# lm2700.net
KiCad netlist of a schematic drawn in Altium Designer
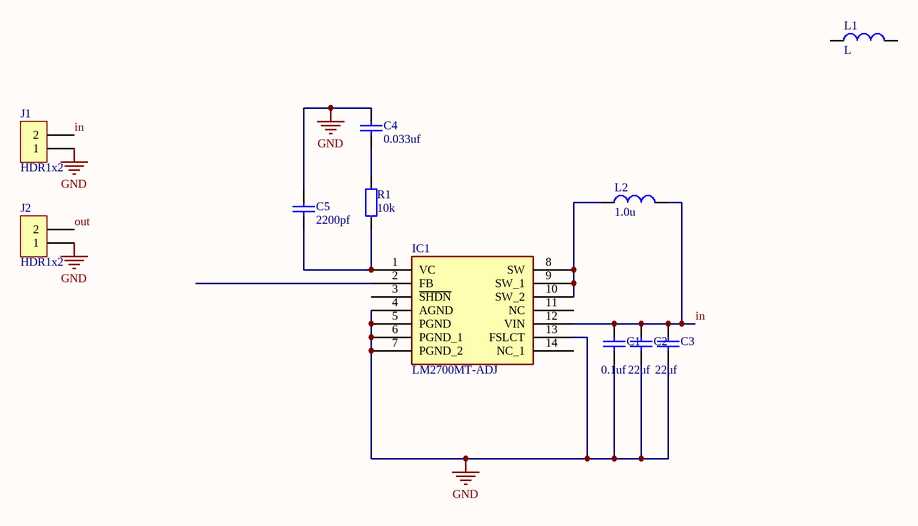
[diagram p0: lm2700.SchDoc]

(export (version "E")
  (design (tool "Eeschema 10.0.6"))
  (components
    (comp (ref "C1")
      (value "0.1uf")
      (footprint "basic:2220")
      (description "电容")
      (libsource (lib "basic") (part "C"))
    )
    (comp (ref "C2")
      (value "22uf")
      (footprint "basic:2220")
      (description "电容")
      (libsource (lib "basic") (part "C"))
    )
    (comp (ref "C3")
      (value "22uf")
      (footprint "basic:2220")
      (description "电容")
      (libsource (lib "basic") (part "C"))
    )
    (comp (ref "C4")
      (value "0.033uf")
      (footprint "basic:2220")
      (description "电容")
      (libsource (lib "basic") (part "C"))
    )
    (comp (ref "C5")
      (value "2200pf")
      (footprint "basic:2220")
      (description "电容")
      (libsource (lib "basic") (part "C"))
    )
    (comp (ref "IC1")
      (value "LM2700MT-ADJ")
      (footprint "SamacSys:SOP65P640X120-14N")
      (description "Integrated Circuit")
      (fields
        (field (name "MOUSER PART NUMBER") "926-LM2700MT-ADJ")
        (field (name "RS PART NUMBER") "4432079")
      )
      (libsource (lib "SamacSys") (part "LM2700MT-ADJ"))
    )
    (comp (ref "J1")
      (value "HDR1x2")
      (footprint "PIN-2-2.54-1.0")
      (description "Connector")
      (libsource (lib "General") (part "HDR1x2"))
    )
    (comp (ref "J2")
      (value "HDR1x2")
      (footprint "PIN-2-2.54-1.0")
      (description "Connector")
      (libsource (lib "General") (part "HDR1x2"))
    )
    (comp (ref "L1")
      (value "L")
      (footprint "L4R7")
      (description "大号贴片电感")
      (libsource (lib "basic") (part "L"))
    )
    (comp (ref "L2")
      (value "1.0u")
      (footprint "L4R7")
      (description "大号贴片电感")
      (libsource (lib "basic") (part "L"))
    )
    (comp (ref "R1")
      (value "10k")
      (footprint "basic:2220")
      (description "电阻")
      (libsource (lib "basic") (part "R"))
    )
  )
  (nets
    (net (code "1") (name "/in") (class "Default")
      (node (ref "C1") (pin "2") (pinfunction "2_2") (pintype "passive"))
      (node (ref "C2") (pin "2") (pinfunction "2_2") (pintype "passive"))
      (node (ref "C3") (pin "2") (pinfunction "2_2") (pintype "passive"))
      (node (ref "IC1") (pin "12") (pinfunction "VIN_12") (pintype "passive"))
      (node (ref "J1") (pin "2") (pinfunction "2_2") (pintype "passive"))
      (node (ref "L2") (pin "2") (pinfunction "2_2") (pintype "passive"))
    )
    (net (code "2") (name "/out") (class "Default")
      (node (ref "J2") (pin "2") (pinfunction "2_2") (pintype "passive"))
    )
    (net (code "3") (name "GND") (class "Default")
      (node (ref "C1") (pin "1") (pinfunction "1_1") (pintype "passive"))
      (node (ref "C2") (pin "1") (pinfunction "1_1") (pintype "passive"))
      (node (ref "C3") (pin "1") (pinfunction "1_1") (pintype "passive"))
      (node (ref "C4") (pin "2") (pinfunction "2_2") (pintype "passive"))
      (node (ref "C5") (pin "2") (pinfunction "2_2") (pintype "passive"))
      (node (ref "IC1") (pin "13") (pinfunction "FSLCT_13") (pintype "passive"))
      (node (ref "IC1") (pin "4") (pinfunction "AGND_4") (pintype "power_in"))
      (node (ref "IC1") (pin "5") (pinfunction "PGND_5") (pintype "power_in"))
      (node (ref "IC1") (pin "6") (pinfunction "PGND_1_6") (pintype "power_in"))
      (node (ref "IC1") (pin "7") (pinfunction "PGND_2_7") (pintype "power_in"))
      (node (ref "J1") (pin "1") (pinfunction "1_1") (pintype "passive"))
      (node (ref "J2") (pin "1") (pinfunction "1_1") (pintype "passive"))
    )
    (net (code "4") (name "Net-(C4-Pad1)") (class "Default")
      (node (ref "C4") (pin "1") (pinfunction "1_1") (pintype "passive"))
      (node (ref "R1") (pin "2") (pinfunction "2_2") (pintype "passive"))
    )
    (net (code "5") (name "Net-(IC1-SW)") (class "Default")
      (node (ref "IC1") (pin "10") (pinfunction "SW_2_10") (pintype "passive"))
      (node (ref "IC1") (pin "8") (pinfunction "SW_8") (pintype "passive"))
      (node (ref "IC1") (pin "9") (pinfunction "SW_1_9") (pintype "passive"))
      (node (ref "L2") (pin "1") (pinfunction "1_1") (pintype "passive"))
    )
    (net (code "6") (name "Net-(IC1-VC)") (class "Default")
      (node (ref "C5") (pin "1") (pinfunction "1_1") (pintype "passive"))
      (node (ref "IC1") (pin "1") (pinfunction "VC_1") (pintype "passive"))
      (node (ref "R1") (pin "1") (pinfunction "1_1") (pintype "passive"))
    )
    (net (code "7") (name "unconnected-(IC1-FB-Pad2)") (class "Default")
      (node (ref "IC1") (pin "2") (pinfunction "FB_2") (pintype "passive"))
    )
    (net (code "8") (name "unconnected-(IC1-NC-Pad11)") (class "Default")
      (node (ref "IC1") (pin "11") (pinfunction "NC_11") (pintype "passive"))
    )
    (net (code "9") (name "unconnected-(IC1-NC_1-Pad14)") (class "Default")
      (node (ref "IC1") (pin "14") (pinfunction "NC_1_14") (pintype "passive"))
    )
    (net (code "10") (name "unconnected-(IC1-~{SHDN}-Pad3)") (class "Default")
      (node (ref "IC1") (pin "3") (pinfunction "~{SHDN}_3") (pintype "passive"))
    )
    (net (code "11") (name "unconnected-(L1-Pad1)") (class "Default")
      (node (ref "L1") (pin "1") (pinfunction "1_1") (pintype "passive"))
    )
    (net (code "12") (name "unconnected-(L1-Pad2)") (class "Default")
      (node (ref "L1") (pin "2") (pinfunction "2_2") (pintype "passive"))
    )
  )
)
